# 4_BLE-T1_power.net
KiCad netlist of a schematic drawn in Altium Designer
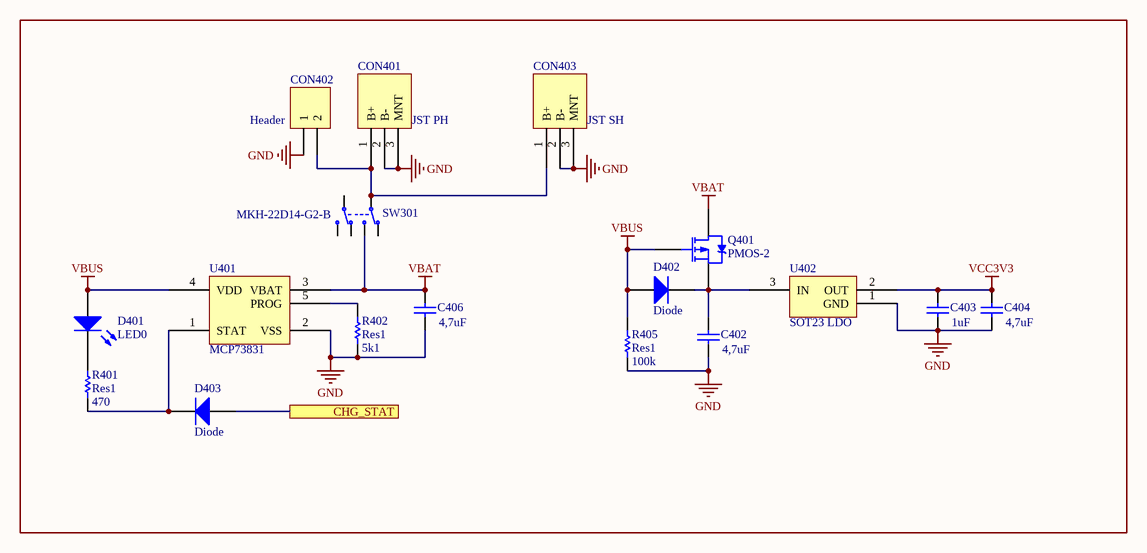
[diagram p0: 4_BLE-T1_power.SchDoc]

(export (version "E")
  (design (tool "Eeschema 10.0.6"))
  (components
    (comp (ref "C402")
      (value "4,7uF")
      (footprint "C0603[1608]")
      (description "Capacitor")
      (fields (field (name "LCSC PART #") "C19666") (field (name "MRF.PART") "CL10A475KO8NNNC"))
      (libsource (lib "Miscellaneous Devices") (part "Cap"))
    )
    (comp (ref "C403")
      (value "1uF")
      (footprint "C0603[1608]")
      (description "Capacitor")
      (fields (field (name "MFG") "KEMET") (field (name "LCSC PART #") "C15849"))
      (libsource (lib "Miscellaneous Devices") (part "Cap"))
    )
    (comp (ref "C404")
      (value "4,7uF")
      (footprint "C0603[1608]")
      (description "Capacitor")
      (fields (field (name "LCSC PART #") "C19666") (field (name "MRF.PART") "CL10A475KO8NNNC"))
      (libsource (lib "Miscellaneous Devices") (part "Cap"))
    )
    (comp (ref "C406")
      (value "4,7uF")
      (footprint "C0603[1608]")
      (description "Capacitor")
      (fields (field (name "LCSC PART #") "C19666") (field (name "MRF.PART") "CL10A475KO8NNNC"))
      (libsource (lib "Miscellaneous Devices") (part "Cap"))
    )
    (comp (ref "CON401")
      (value "JST PH")
      (footprint "JST S2B-PH-SM4-TB")
      (fields (field (name "MFG") "JST Sales America Inc."))
      (libsource (lib "Keebs") (part "JST S2B-PH-SM4-TB"))
    )
    (comp (ref "CON402")
      (value "Header")
      (footprint "HDR1X2")
      (description "Header, 2-Pin")
      (libsource (lib "Miscellaneous Connectors") (part "Header 2"))
    )
    (comp (ref "CON403")
      (value "JST SH")
      (footprint "JST SM02B-SRSS-TB")
      (fields (field (name "MFG") "JST Sales America Inc."))
      (libsource (lib "Keebs") (part "JST S2B-PH-SM4-TB"))
    )
    (comp (ref "D401")
      (value "LED0")
      (footprint "LED0603[1608]")
      (description "Typical INFRARED GaAs LED")
      (fields (field (name "MFG") "Kingbright"))
      (libsource (lib "Miscellaneous Devices") (part "LED0"))
    )
    (comp (ref "D402")
      (value "Diode")
      (footprint "SOD-123")
      (description "Default Diode")
      (fields (field (name "LCSC PART #") "C8598") (field (name "MRF.PART") "B5819W"))
      (libsource (lib "Miscellaneous Devices") (part "Diode"))
    )
    (comp (ref "D403")
      (value "Diode")
      (footprint "SOD-123")
      (description "Default Diode")
      (fields (field (name "LCSC PART #") "C8598") (field (name "MRF.PART") "B5819W"))
      (libsource (lib "Miscellaneous Devices") (part "Diode"))
    )
    (comp (ref "Q401")
      (value "PMOS-2")
      (footprint "SOT-23-3")
      (description "P-Channel Power MOSFET")
      (fields (field (name "MRF.PART") "SI2301CDS-T1-GE3") (field (name "LCSC PART #") "C10487"))
      (libsource (lib "Miscellaneous Devices") (part "PMOS-2"))
    )
    (comp (ref "R401")
      (value "Res1")
      (footprint "R0603[1608]")
      (description "Resistor")
      (fields
        (field (name "ALTIUM_VALUE") "470")
        (field (name "MFG") "Panasonic Electronic Components")
        (field (name "LCSC PART #") "C23179")
      )
      (libsource (lib "Miscellaneous Devices") (part "Res1"))
    )
    (comp (ref "R402")
      (value "Res1")
      (footprint "R0603[1608]")
      (description "Resistor")
      (fields
        (field (name "ALTIUM_VALUE") "5k1")
        (field (name "LCSC PART #") "C23186")
        (field (name "MRF.PART") "0603WAF5101T5E")
      )
      (libsource (lib "Miscellaneous Devices") (part "Res1"))
    )
    (comp (ref "R405")
      (value "Res1")
      (footprint "R0603[1608]")
      (description "Resistor")
      (fields
        (field (name "ALTIUM_VALUE") "100k")
        (field (name "MRF.PART") "0603WAF1003T5E")
        (field (name "LCSC PART #") "C25803")
      )
      (libsource (lib "Miscellaneous Devices") (part "Res1"))
    )
    (comp (ref "SW301")
      (value "MKH-22D14-G2-B")
      (footprint "MKH-22D14-G2-B")
      (description "Slide Switch DPDT")
      (fields (field (name "MFG") "Nidec Copal Electronics"))
      (libsource (lib "Keebs") (part "MKH-22D14-G2-B"))
    )
    (comp (ref "U401") (value "MCP73831") (footprint "SOT-23-5") (libsource (lib "Keebs") (part "MCP73831")))
    (comp (ref "U402")
      (value "SOT23 LDO")
      (footprint "SOT-23-3")
      (fields
        (field (name "LCSC PART #") "C5446")
        (field (name "MRF.PART") "XC6206P332MR")
        (field (name "MFG") "Texas Instruments")
      )
      (libsource (lib "Keebs") (part "SOT23 LDO"))
    )
  )
  (nets
    (net (code "1") (name "/CHG_STAT") (class "Default")
      (node (ref "D403") (pin "1") (pinfunction "A_1") (pintype "passive"))
    )
    (net (code "2") (name "GND") (class "Default")
      (node (ref "C402") (pin "1") (pinfunction "1_1") (pintype "passive"))
      (node (ref "C403") (pin "1") (pinfunction "1_1") (pintype "passive"))
      (node (ref "C404") (pin "1") (pinfunction "1_1") (pintype "passive"))
      (node (ref "C406") (pin "1") (pinfunction "1_1") (pintype "passive"))
      (node (ref "CON401") (pin "2") (pinfunction "B-_2") (pintype "passive"))
      (node (ref "CON401") (pin "3") (pinfunction "MNT_3") (pintype "passive"))
      (node (ref "CON402") (pin "1") (pinfunction "1_1") (pintype "passive"))
      (node (ref "CON403") (pin "2") (pinfunction "B-_2") (pintype "passive"))
      (node (ref "CON403") (pin "3") (pinfunction "MNT_3") (pintype "passive"))
      (node (ref "R402") (pin "2") (pinfunction "2_2") (pintype "passive"))
      (node (ref "R405") (pin "2") (pinfunction "2_2") (pintype "passive"))
      (node (ref "U401") (pin "2") (pinfunction "VSS_2") (pintype "passive"))
      (node (ref "U402") (pin "1") (pinfunction "GND_1") (pintype "passive"))
    )
    (net (code "3") (name "Net-(CON401-B+)") (class "Default")
      (node (ref "CON401") (pin "1") (pinfunction "B+_1") (pintype "passive"))
      (node (ref "CON402") (pin "2") (pinfunction "2_2") (pintype "passive"))
      (node (ref "CON403") (pin "1") (pinfunction "B+_1") (pintype "passive"))
      (node (ref "SW301") (pin "2") (pinfunction "COM-1_2") (pintype "passive"))
    )
    (net (code "4") (name "Net-(D401-K)") (class "Default")
      (node (ref "D401") (pin "2") (pinfunction "K_2") (pintype "passive"))
      (node (ref "R401") (pin "2") (pinfunction "2_2") (pintype "passive"))
    )
    (net (code "5") (name "Net-(D402-K)") (class "Default")
      (node (ref "C402") (pin "2") (pinfunction "2_2") (pintype "passive"))
      (node (ref "D402") (pin "2") (pinfunction "K_2") (pintype "passive"))
      (node (ref "Q401") (pin "2") (pinfunction "S_2") (pintype "passive"))
      (node (ref "U402") (pin "3") (pinfunction "IN_3") (pintype "passive"))
    )
    (net (code "6") (name "Net-(D403-K)") (class "Default")
      (node (ref "D403") (pin "2") (pinfunction "K_2") (pintype "passive"))
      (node (ref "R401") (pin "1") (pinfunction "1_1") (pintype "passive"))
      (node (ref "U401") (pin "1") (pinfunction "STAT_1") (pintype "passive"))
    )
    (net (code "7") (name "Net-(U401-PROG)") (class "Default")
      (node (ref "R402") (pin "1") (pinfunction "1_1") (pintype "passive"))
      (node (ref "U401") (pin "5") (pinfunction "PROG_5") (pintype "passive"))
    )
    (net (code "8") (name "VBAT") (class "Default")
      (node (ref "C406") (pin "2") (pinfunction "2_2") (pintype "passive"))
      (node (ref "Q401") (pin "3") (pinfunction "D_3") (pintype "passive"))
      (node (ref "SW301") (pin "1") (pinfunction "N.O-1_1") (pintype "passive"))
      (node (ref "U401") (pin "3") (pinfunction "VBAT_3") (pintype "passive"))
    )
    (net (code "9") (name "VBUS") (class "Default")
      (node (ref "D401") (pin "1") (pinfunction "A_1") (pintype "passive"))
      (node (ref "D402") (pin "1") (pinfunction "A_1") (pintype "passive"))
      (node (ref "Q401") (pin "1") (pinfunction "G_1") (pintype "passive"))
      (node (ref "R405") (pin "1") (pinfunction "1_1") (pintype "passive"))
      (node (ref "U401") (pin "4") (pinfunction "VDD_4") (pintype "passive"))
    )
    (net (code "10") (name "VCC3V3") (class "Default")
      (node (ref "C403") (pin "2") (pinfunction "2_2") (pintype "passive"))
      (node (ref "C404") (pin "2") (pinfunction "2_2") (pintype "passive"))
      (node (ref "U402") (pin "2") (pinfunction "OUT_2") (pintype "passive"))
    )
    (net (code "11") (name "unconnected-(SW301-COM-2-Pad5)") (class "Default")
      (node (ref "SW301") (pin "5") (pinfunction "COM-2_5") (pintype "passive"))
    )
    (net (code "12") (name "unconnected-(SW301-N.C-1-Pad3)") (class "Default")
      (node (ref "SW301") (pin "3") (pinfunction "N.C-1_3") (pintype "passive"))
    )
    (net (code "13") (name "unconnected-(SW301-N.C-2-Pad6)") (class "Default")
      (node (ref "SW301") (pin "6") (pinfunction "N.C-2_6") (pintype "passive"))
    )
    (net (code "14") (name "unconnected-(SW301-N.O-2-Pad4)") (class "Default")
      (node (ref "SW301") (pin "4") (pinfunction "N.O-2_4") (pintype "passive"))
    )
  )
)
